# Sheet2.net
KiCad netlist of a schematic drawn in Altium Designer
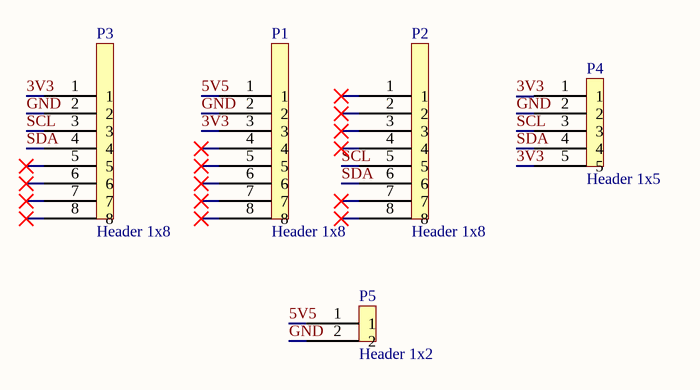
[diagram p0: Sheet2.SchDoc]

(export (version "E")
  (design (tool "Eeschema 10.0.6"))
  (components
    (comp (ref "P1")
      (value "Header 1x8")
      (footprint "HDR1x8 2.54mm")
      (libsource (lib "Physio_Symbols") (part "Header 1x8"))
    )
    (comp (ref "P2")
      (value "Header 1x8")
      (footprint "HDR1x8 2.54mm")
      (libsource (lib "Physio_Symbols") (part "Header 1x8"))
    )
    (comp (ref "P3")
      (value "Header 1x8")
      (footprint "HDR1x8 2.54mm")
      (libsource (lib "Physio_Symbols") (part "Header 1x8"))
    )
    (comp (ref "P4")
      (value "Header 1x5")
      (footprint "HDR1x5 2.54mm")
      (libsource (lib "Physio_Symbols") (part "Header 1x5"))
    )
    (comp (ref "P5")
      (value "Header 1x2")
      (footprint "HDR1x2 2.54MM")
      (libsource (lib "Physio_Symbols") (part "Header 1x2"))
    )
  )
  (nets
    (net (code "1") (name "/3V3") (class "Default")
      (node (ref "P1") (pin "3") (pinfunction "3_3") (pintype "passive"))
      (node (ref "P3") (pin "1") (pinfunction "1_1") (pintype "passive"))
      (node (ref "P4") (pin "1") (pinfunction "1_1") (pintype "passive"))
      (node (ref "P4") (pin "5") (pinfunction "5_5") (pintype "passive"))
    )
    (net (code "2") (name "/5V5") (class "Default")
      (node (ref "P1") (pin "1") (pinfunction "1_1") (pintype "passive"))
      (node (ref "P5") (pin "1") (pinfunction "1_1") (pintype "passive"))
    )
    (net (code "3") (name "/GND") (class "Default")
      (node (ref "P1") (pin "2") (pinfunction "2_2") (pintype "passive"))
      (node (ref "P3") (pin "2") (pinfunction "2_2") (pintype "passive"))
      (node (ref "P4") (pin "2") (pinfunction "2_2") (pintype "passive"))
      (node (ref "P5") (pin "2") (pinfunction "2_2") (pintype "passive"))
    )
    (net (code "4") (name "/SCL") (class "Default")
      (node (ref "P2") (pin "5") (pinfunction "5_5") (pintype "passive"))
      (node (ref "P3") (pin "3") (pinfunction "3_3") (pintype "passive"))
      (node (ref "P4") (pin "3") (pinfunction "3_3") (pintype "passive"))
    )
    (net (code "5") (name "/SDA") (class "Default")
      (node (ref "P2") (pin "6") (pinfunction "6_6") (pintype "passive"))
      (node (ref "P3") (pin "4") (pinfunction "4_4") (pintype "passive"))
      (node (ref "P4") (pin "4") (pinfunction "4_4") (pintype "passive"))
    )
    (net (code "6") (name "unconnected-(P1-Pad4)") (class "Default")
      (node (ref "P1") (pin "4") (pinfunction "4_4") (pintype "passive+no_connect"))
    )
    (net (code "7") (name "unconnected-(P1-Pad5)") (class "Default")
      (node (ref "P1") (pin "5") (pinfunction "5_5") (pintype "passive+no_connect"))
    )
    (net (code "8") (name "unconnected-(P1-Pad6)") (class "Default")
      (node (ref "P1") (pin "6") (pinfunction "6_6") (pintype "passive+no_connect"))
    )
    (net (code "9") (name "unconnected-(P1-Pad7)") (class "Default")
      (node (ref "P1") (pin "7") (pinfunction "7_7") (pintype "passive+no_connect"))
    )
    (net (code "10") (name "unconnected-(P1-Pad8)") (class "Default")
      (node (ref "P1") (pin "8") (pinfunction "8_8") (pintype "passive+no_connect"))
    )
    (net (code "11") (name "unconnected-(P2-Pad1)") (class "Default")
      (node (ref "P2") (pin "1") (pinfunction "1_1") (pintype "passive+no_connect"))
    )
    (net (code "12") (name "unconnected-(P2-Pad2)") (class "Default")
      (node (ref "P2") (pin "2") (pinfunction "2_2") (pintype "passive+no_connect"))
    )
    (net (code "13") (name "unconnected-(P2-Pad3)") (class "Default")
      (node (ref "P2") (pin "3") (pinfunction "3_3") (pintype "passive+no_connect"))
    )
    (net (code "14") (name "unconnected-(P2-Pad4)") (class "Default")
      (node (ref "P2") (pin "4") (pinfunction "4_4") (pintype "passive+no_connect"))
    )
    (net (code "15") (name "unconnected-(P2-Pad7)") (class "Default")
      (node (ref "P2") (pin "7") (pinfunction "7_7") (pintype "passive+no_connect"))
    )
    (net (code "16") (name "unconnected-(P2-Pad8)") (class "Default")
      (node (ref "P2") (pin "8") (pinfunction "8_8") (pintype "passive+no_connect"))
    )
    (net (code "17") (name "unconnected-(P3-Pad5)") (class "Default")
      (node (ref "P3") (pin "5") (pinfunction "5_5") (pintype "passive+no_connect"))
    )
    (net (code "18") (name "unconnected-(P3-Pad6)") (class "Default")
      (node (ref "P3") (pin "6") (pinfunction "6_6") (pintype "passive+no_connect"))
    )
    (net (code "19") (name "unconnected-(P3-Pad7)") (class "Default")
      (node (ref "P3") (pin "7") (pinfunction "7_7") (pintype "passive+no_connect"))
    )
    (net (code "20") (name "unconnected-(P3-Pad8)") (class "Default")
      (node (ref "P3") (pin "8") (pinfunction "8_8") (pintype "passive+no_connect"))
    )
  )
)
